# FOC_4.net
KiCad netlist of a schematic drawn in Altium Designer
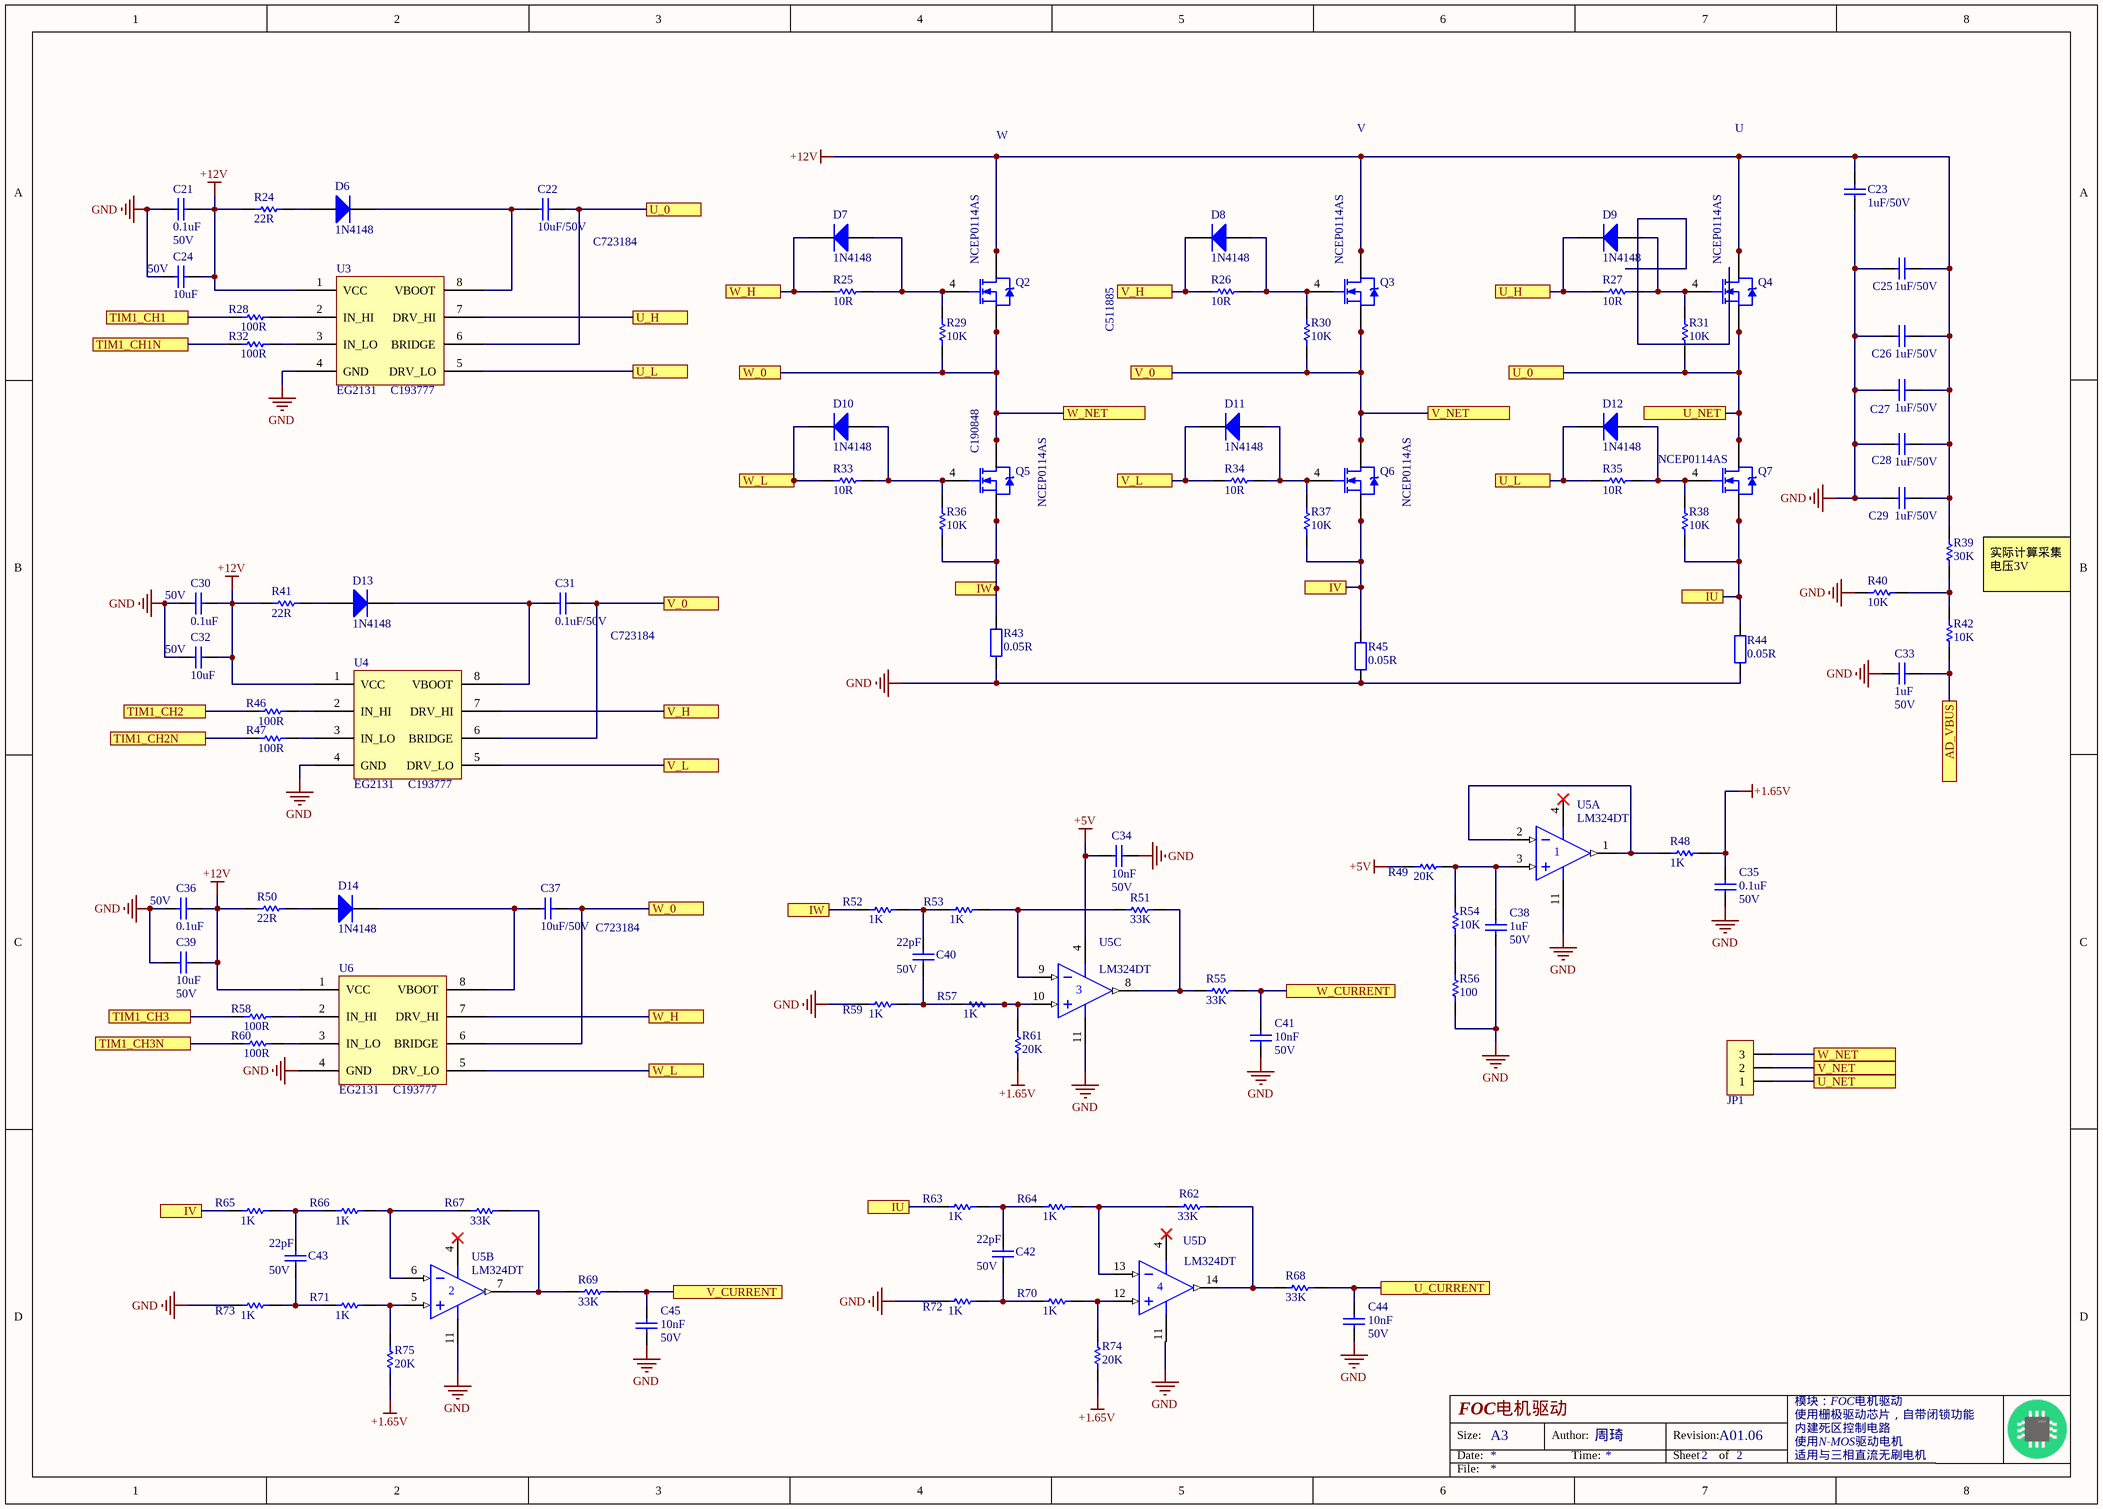
[diagram p0: FOC_4.SchDoc]

(export (version "E")
  (design (tool "Eeschema 10.0.6"))
  (components
    (comp (ref "C21")
      (value "0.1uF")
      (footprint "C0603_L")
      (fields (field (name "PARM") "50V"))
      (libsource (lib "Miscellaneous Devices") (part "Cap"))
    )
    (comp (ref "C22")
      (value "10uF/50V")
      (footprint "C0603_L")
      (description "C89632")
      (libsource (lib "Miscellaneous Devices") (part "Cap"))
    )
    (comp (ref "C23")
      (value "1uF/50V")
      (footprint "C1210_L")
      (libsource (lib "Miscellaneous Devices") (part "Cap"))
    )
    (comp (ref "C24")
      (value "10uF")
      (footprint "C0805_L")
      (fields (field (name "PARM") "50V"))
      (libsource (lib "Miscellaneous Devices") (part "Cap"))
    )
    (comp (ref "C25")
      (value "1uF/50V")
      (footprint "C1210_L")
      (libsource (lib "Miscellaneous Devices") (part "Cap"))
    )
    (comp (ref "C26")
      (value "1uF/50V")
      (footprint "C1210_L")
      (libsource (lib "Miscellaneous Devices") (part "Cap"))
    )
    (comp (ref "C27")
      (value "1uF/50V")
      (footprint "C1210_L")
      (libsource (lib "Miscellaneous Devices") (part "Cap"))
    )
    (comp (ref "C28")
      (value "1uF/50V")
      (footprint "C1210_L")
      (libsource (lib "Miscellaneous Devices") (part "Cap"))
    )
    (comp (ref "C29")
      (value "1uF/50V")
      (footprint "C1210_L")
      (libsource (lib "Miscellaneous Devices") (part "Cap"))
    )
    (comp (ref "C30")
      (value "0.1uF")
      (footprint "C0603_L")
      (fields (field (name "PARM") "50V"))
      (libsource (lib "Miscellaneous Devices") (part "Cap"))
    )
    (comp (ref "C31")
      (value "0.1uF/50V")
      (footprint "C0603_L")
      (description "C89632")
      (libsource (lib "Miscellaneous Devices") (part "Cap"))
    )
    (comp (ref "C32")
      (value "10uF")
      (footprint "C0805_L")
      (fields (field (name "PARM") "50V"))
      (libsource (lib "Miscellaneous Devices") (part "Cap"))
    )
    (comp (ref "C33")
      (value "1uF")
      (footprint "C0603_L")
      (fields (field (name "PARM") "50V"))
      (libsource (lib "Miscellaneous Devices") (part "Cap"))
    )
    (comp (ref "C34")
      (value "10nF")
      (footprint "C0603_L")
      (fields (field (name "PARM") "50V"))
      (libsource (lib "Miscellaneous Devices") (part "Cap"))
    )
    (comp (ref "C35")
      (value "0.1uF")
      (footprint "C0603_L")
      (fields (field (name "PARM") "50V"))
      (libsource (lib "Miscellaneous Devices") (part "Cap"))
    )
    (comp (ref "C36")
      (value "0.1uF")
      (footprint "C0603_L")
      (fields (field (name "PARM") "50V"))
      (libsource (lib "Miscellaneous Devices") (part "Cap"))
    )
    (comp (ref "C37")
      (value "10uF/50V")
      (footprint "C0603_L")
      (description "C89632")
      (libsource (lib "Miscellaneous Devices") (part "Cap"))
    )
    (comp (ref "C38")
      (value "1uF")
      (footprint "C0603_L")
      (fields (field (name "PARM") "50V"))
      (libsource (lib "Miscellaneous Devices") (part "Cap"))
    )
    (comp (ref "C39")
      (value "10uF")
      (footprint "C0805_L")
      (fields (field (name "PARM") "50V"))
      (libsource (lib "Miscellaneous Devices") (part "Cap"))
    )
    (comp (ref "C40")
      (value "22pF")
      (footprint "C0603_L")
      (fields (field (name "PARM") "50V"))
      (libsource (lib "Miscellaneous Devices") (part "Cap"))
    )
    (comp (ref "C41")
      (value "10nF")
      (footprint "C0603_L")
      (fields (field (name "PARM") "50V"))
      (libsource (lib "Miscellaneous Devices") (part "Cap"))
    )
    (comp (ref "C42")
      (value "22pF")
      (footprint "C0603_L")
      (fields (field (name "PARM") "50V"))
      (libsource (lib "Miscellaneous Devices") (part "Cap"))
    )
    (comp (ref "C43")
      (value "22pF")
      (footprint "C0603_L")
      (fields (field (name "PARM") "50V"))
      (libsource (lib "Miscellaneous Devices") (part "Cap"))
    )
    (comp (ref "C44")
      (value "10nF")
      (footprint "C0603_L")
      (fields (field (name "PARM") "50V"))
      (libsource (lib "Miscellaneous Devices") (part "Cap"))
    )
    (comp (ref "C45")
      (value "10nF")
      (footprint "C0603_L")
      (fields (field (name "PARM") "50V"))
      (libsource (lib "Miscellaneous Devices") (part "Cap"))
    )
    (comp (ref "D6")
      (value "1N4148")
      (footprint "SOD-123")
      (description "二极管")
      (libsource (lib "Miscellaneous Devices LC") (part "SOD-323 1N4148WS T4"))
    )
    (comp (ref "D7")
      (value "1N4148")
      (footprint "SOD-123")
      (description "二极管")
      (libsource (lib "Miscellaneous Devices LC") (part "SOD-323 1N4148WS T4"))
    )
    (comp (ref "D8")
      (value "1N4148")
      (footprint "SOD-123")
      (description "二极管")
      (libsource (lib "Miscellaneous Devices LC") (part "SOD-323 1N4148WS T4"))
    )
    (comp (ref "D9")
      (value "1N4148")
      (footprint "SOD-123")
      (description "二极管")
      (libsource (lib "Miscellaneous Devices LC") (part "SOD-323 1N4148WS T4"))
    )
    (comp (ref "D10")
      (value "1N4148")
      (footprint "SOD-123")
      (description "二极管")
      (libsource (lib "Miscellaneous Devices LC") (part "SOD-323 1N4148WS T4"))
    )
    (comp (ref "D11")
      (value "1N4148")
      (footprint "SOD-123")
      (description "二极管")
      (libsource (lib "Miscellaneous Devices LC") (part "SOD-323 1N4148WS T4"))
    )
    (comp (ref "D12")
      (value "1N4148")
      (footprint "SOD-123")
      (description "二极管")
      (libsource (lib "Miscellaneous Devices LC") (part "SOD-323 1N4148WS T4"))
    )
    (comp (ref "D13")
      (value "1N4148")
      (footprint "SOD-123")
      (description "二极管")
      (libsource (lib "Miscellaneous Devices LC") (part "SOD-323 1N4148WS T4"))
    )
    (comp (ref "D14")
      (value "1N4148")
      (footprint "SOD-123")
      (description "二极管")
      (libsource (lib "Miscellaneous Devices LC") (part "SOD-323 1N4148WS T4"))
    )
    (comp (ref "JP1")
      (value "HDR-1X3")
      (footprint "KF350-3P")
      (description "3P接插件")
      (fields (field (name "版权归属") "源创客"))
      (libsource (lib "接插件") (part "Header 3"))
    )
    (comp (ref "Q2")
      (value "NCEP0114AS")
      (footprint "SOP8")
      (description "C190848")
      (fields (field (name "PUBLISHER") "60V"))
      (libsource (lib "Miscellaneous Devices") (part "NMOS-2"))
    )
    (comp (ref "Q3")
      (value "NCEP0114AS")
      (footprint "SOP8")
      (description "C190848")
      (fields (field (name "PUBLISHER") "60V"))
      (libsource (lib "Miscellaneous Devices") (part "NMOS-2"))
    )
    (comp (ref "Q4")
      (value "NCEP0114AS")
      (footprint "SOP8")
      (description "C190848")
      (fields (field (name "PUBLISHER") "60V"))
      (libsource (lib "Miscellaneous Devices") (part "NMOS-2"))
    )
    (comp (ref "Q5")
      (value "NCEP0114AS")
      (footprint "SOP8")
      (description "C190848")
      (fields (field (name "PUBLISHER") "60V"))
      (libsource (lib "Miscellaneous Devices") (part "NMOS-2"))
    )
    (comp (ref "Q6")
      (value "NCEP0114AS")
      (footprint "SOP8")
      (description "C190848")
      (fields (field (name "PUBLISHER") "60V"))
      (libsource (lib "Miscellaneous Devices") (part "NMOS-2"))
    )
    (comp (ref "Q7")
      (value "NCEP0114AS")
      (footprint "SOP8")
      (description "C190848")
      (fields (field (name "PUBLISHER") "60V"))
      (libsource (lib "Miscellaneous Devices") (part "NMOS-2"))
    )
    (comp (ref "R24")
      (value "22R")
      (footprint "R0603_L")
      (description "Resistor")
      (libsource (lib "Miscellaneous Devices") (part "Res1"))
    )
    (comp (ref "R25")
      (value "10R")
      (footprint "R0603_L")
      (description "Resistor")
      (libsource (lib "Miscellaneous Devices") (part "Res1"))
    )
    (comp (ref "R26")
      (value "10R")
      (footprint "R0603_L")
      (description "Resistor")
      (libsource (lib "Miscellaneous Devices") (part "Res1"))
    )
    (comp (ref "R27")
      (value "10R")
      (footprint "R0603_L")
      (description "Resistor")
      (libsource (lib "Miscellaneous Devices") (part "Res1"))
    )
    (comp (ref "R28")
      (value "100R")
      (footprint "R0603_L")
      (description "Resistor")
      (libsource (lib "Miscellaneous Devices") (part "Res1"))
    )
    (comp (ref "R29")
      (value "10K")
      (footprint "R0603_L")
      (description "Resistor")
      (libsource (lib "Miscellaneous Devices") (part "Res1"))
    )
    (comp (ref "R30")
      (value "10K")
      (footprint "R0603_L")
      (description "Resistor")
      (libsource (lib "Miscellaneous Devices") (part "Res1"))
    )
    (comp (ref "R31")
      (value "10K")
      (footprint "R0603_L")
      (description "Resistor")
      (libsource (lib "Miscellaneous Devices") (part "Res1"))
    )
    (comp (ref "R32")
      (value "100R")
      (footprint "R0603_L")
      (description "Resistor")
      (libsource (lib "Miscellaneous Devices") (part "Res1"))
    )
    (comp (ref "R33")
      (value "10R")
      (footprint "R0603_L")
      (description "Resistor")
      (libsource (lib "Miscellaneous Devices") (part "Res1"))
    )
    (comp (ref "R34")
      (value "10R")
      (footprint "R0603_L")
      (description "Resistor")
      (libsource (lib "Miscellaneous Devices") (part "Res1"))
    )
    (comp (ref "R35")
      (value "10R")
      (footprint "R0603_L")
      (description "Resistor")
      (libsource (lib "Miscellaneous Devices") (part "Res1"))
    )
    (comp (ref "R36")
      (value "10K")
      (footprint "R0603_L")
      (description "Resistor")
      (libsource (lib "Miscellaneous Devices") (part "Res1"))
    )
    (comp (ref "R37")
      (value "10K")
      (footprint "R0603_L")
      (description "Resistor")
      (libsource (lib "Miscellaneous Devices") (part "Res1"))
    )
    (comp (ref "R38")
      (value "10K")
      (footprint "R0603_L")
      (description "Resistor")
      (libsource (lib "Miscellaneous Devices") (part "Res1"))
    )
    (comp (ref "R39")
      (value "30K")
      (footprint "R0603_L")
      (description "Resistor")
      (libsource (lib "Miscellaneous Devices") (part "Res1"))
    )
    (comp (ref "R40")
      (value "10K")
      (footprint "R0603_L")
      (description "Resistor")
      (libsource (lib "Miscellaneous Devices") (part "Res1"))
    )
    (comp (ref "R41")
      (value "22R")
      (footprint "R0603_L")
      (description "Resistor")
      (libsource (lib "Miscellaneous Devices") (part "Res1"))
    )
    (comp (ref "R42")
      (value "10K")
      (footprint "R0603_L")
      (description "Resistor")
      (libsource (lib "Miscellaneous Devices") (part "Res1"))
    )
    (comp (ref "R43")
      (value "0.05R")
      (footprint "R2512_L")
      (description "电流检测电阻")
      (fields (field (name "版权归属") "源创客"))
      (libsource (lib "电阻-电容-电感") (part "R-I"))
    )
    (comp (ref "R44")
      (value "0.05R")
      (footprint "R2512_L")
      (description "电流检测电阻")
      (fields (field (name "版权归属") "源创客"))
      (libsource (lib "电阻-电容-电感") (part "R-I"))
    )
    (comp (ref "R45")
      (value "0.05R")
      (footprint "R2512_L")
      (description "电流检测电阻")
      (fields (field (name "版权归属") "源创客"))
      (libsource (lib "电阻-电容-电感") (part "R-I"))
    )
    (comp (ref "R46")
      (value "100R")
      (footprint "R0603_L")
      (description "Resistor")
      (libsource (lib "Miscellaneous Devices") (part "Res1"))
    )
    (comp (ref "R47")
      (value "100R")
      (footprint "R0603_L")
      (description "Resistor")
      (libsource (lib "Miscellaneous Devices") (part "Res1"))
    )
    (comp (ref "R48")
      (value "1K")
      (footprint "R0603_L")
      (description "Resistor")
      (libsource (lib "Miscellaneous Devices") (part "Res1"))
    )
    (comp (ref "R49")
      (value "20K")
      (footprint "R0603_L")
      (description "Resistor")
      (libsource (lib "Miscellaneous Devices") (part "Res1"))
    )
    (comp (ref "R50")
      (value "22R")
      (footprint "R0603_L")
      (description "Resistor")
      (libsource (lib "Miscellaneous Devices") (part "Res1"))
    )
    (comp (ref "R51")
      (value "33K")
      (footprint "R0603_L")
      (description "Resistor")
      (libsource (lib "Miscellaneous Devices") (part "Res1"))
    )
    (comp (ref "R52")
      (value "1K")
      (footprint "R0603_L")
      (description "Resistor")
      (libsource (lib "Miscellaneous Devices") (part "Res1"))
    )
    (comp (ref "R53")
      (value "1K")
      (footprint "R0603_L")
      (description "Resistor")
      (libsource (lib "Miscellaneous Devices") (part "Res1"))
    )
    (comp (ref "R54")
      (value "10K")
      (footprint "R0603_L")
      (description "Resistor")
      (libsource (lib "Miscellaneous Devices") (part "Res1"))
    )
    (comp (ref "R55")
      (value "33K")
      (footprint "R0603_L")
      (description "Resistor")
      (libsource (lib "Miscellaneous Devices") (part "Res1"))
    )
    (comp (ref "R56")
      (value "100")
      (footprint "R0603_L")
      (description "Resistor")
      (libsource (lib "Miscellaneous Devices") (part "Res1"))
    )
    (comp (ref "R57")
      (value "1K")
      (footprint "R0603_L")
      (description "Resistor")
      (libsource (lib "Miscellaneous Devices") (part "Res1"))
    )
    (comp (ref "R58")
      (value "100R")
      (footprint "R0603_L")
      (description "Resistor")
      (libsource (lib "Miscellaneous Devices") (part "Res1"))
    )
    (comp (ref "R59")
      (value "1K")
      (footprint "R0603_L")
      (description "Resistor")
      (libsource (lib "Miscellaneous Devices") (part "Res1"))
    )
    (comp (ref "R60")
      (value "100R")
      (footprint "R0603_L")
      (description "Resistor")
      (libsource (lib "Miscellaneous Devices") (part "Res1"))
    )
    (comp (ref "R61")
      (value "20K")
      (footprint "R0603_L")
      (description "Resistor")
      (libsource (lib "Miscellaneous Devices") (part "Res1"))
    )
    (comp (ref "R62")
      (value "33K")
      (footprint "R0603_L")
      (description "Resistor")
      (libsource (lib "Miscellaneous Devices") (part "Res1"))
    )
    (comp (ref "R63")
      (value "1K")
      (footprint "R0603_L")
      (description "Resistor")
      (libsource (lib "Miscellaneous Devices") (part "Res1"))
    )
    (comp (ref "R64")
      (value "1K")
      (footprint "R0603_L")
      (description "Resistor")
      (libsource (lib "Miscellaneous Devices") (part "Res1"))
    )
    (comp (ref "R65")
      (value "1K")
      (footprint "R0603_L")
      (description "Resistor")
      (libsource (lib "Miscellaneous Devices") (part "Res1"))
    )
    (comp (ref "R66")
      (value "1K")
      (footprint "R0603_L")
      (description "Resistor")
      (libsource (lib "Miscellaneous Devices") (part "Res1"))
    )
    (comp (ref "R67")
      (value "33K")
      (footprint "R0603_L")
      (description "Resistor")
      (libsource (lib "Miscellaneous Devices") (part "Res1"))
    )
    (comp (ref "R68")
      (value "33K")
      (footprint "R0603_L")
      (description "Resistor")
      (libsource (lib "Miscellaneous Devices") (part "Res1"))
    )
    (comp (ref "R69")
      (value "33K")
      (footprint "R0603_L")
      (description "Resistor")
      (libsource (lib "Miscellaneous Devices") (part "Res1"))
    )
    (comp (ref "R70")
      (value "1K")
      (footprint "R0603_L")
      (description "Resistor")
      (libsource (lib "Miscellaneous Devices") (part "Res1"))
    )
    (comp (ref "R71")
      (value "1K")
      (footprint "R0603_L")
      (description "Resistor")
      (libsource (lib "Miscellaneous Devices") (part "Res1"))
    )
    (comp (ref "R72")
      (value "1K")
      (footprint "R0603_L")
      (description "Resistor")
      (libsource (lib "Miscellaneous Devices") (part "Res1"))
    )
    (comp (ref "R73")
      (value "1K")
      (footprint "R0603_L")
      (description "Resistor")
      (libsource (lib "Miscellaneous Devices") (part "Res1"))
    )
    (comp (ref "R74")
      (value "20K")
      (footprint "R0603_L")
      (description "Resistor")
      (libsource (lib "Miscellaneous Devices") (part "Res1"))
    )
    (comp (ref "R75")
      (value "20K")
      (footprint "R0603_L")
      (description "Resistor")
      (libsource (lib "Miscellaneous Devices") (part "Res1"))
    )
    (comp (ref "U3")
      (value "EG2131")
      (footprint "SOP8")
      (description "C193777")
      (fields (field (name "编号") "C193777"))
      (libsource (lib "Tang") (part "NCP5106BDR2G"))
    )
    (comp (ref "U4")
      (value "EG2131")
      (footprint "SOP8")
      (description "C193777")
      (fields (field (name "编号") "C193777"))
      (libsource (lib "Tang") (part "NCP5106BDR2G"))
    )
    (comp (ref "U5")
      (value "LM324DT")
      (footprint "SOIC-14")
      (description "运放")
      (libsource (lib "Miscellaneous Devices LC") (part "LM324DT_[C71035]"))
    )
    (comp (ref "U6")
      (value "EG2131")
      (footprint "SOP8")
      (description "C193777")
      (fields (field (name "编号") "C193777"))
      (libsource (lib "Tang") (part "NCP5106BDR2G"))
    )
  )
  (nets
    (net (code "1") (name "+1.65V") (class "Default")
      (node (ref "C35") (pin "2") (pinfunction "2_2") (pintype "passive"))
      (node (ref "R48") (pin "1") (pinfunction "1_1") (pintype "passive"))
      (node (ref "R61") (pin "1") (pinfunction "1_1") (pintype "passive"))
      (node (ref "R74") (pin "1") (pinfunction "1_1") (pintype "passive"))
      (node (ref "R75") (pin "1") (pinfunction "1_1") (pintype "passive"))
    )
    (net (code "2") (name "+5V") (class "Default")
      (node (ref "C34") (pin "2") (pinfunction "2_2") (pintype "passive"))
      (node (ref "R49") (pin "1") (pinfunction "1_1") (pintype "passive"))
      (node (ref "U5") (pin "4") (pinfunction "V+_4") (pintype "power_in"))
    )
    (net (code "3") (name "+12V") (class "Default")
      (node (ref "C21") (pin "1") (pinfunction "1_1") (pintype "passive"))
      (node (ref "C23") (pin "1") (pinfunction "1_1") (pintype "passive"))
      (node (ref "C24") (pin "1") (pinfunction "1_1") (pintype "passive"))
      (node (ref "C25") (pin "1") (pinfunction "1_1") (pintype "passive"))
      (node (ref "C26") (pin "1") (pinfunction "1_1") (pintype "passive"))
      (node (ref "C27") (pin "1") (pinfunction "1_1") (pintype "passive"))
      (node (ref "C28") (pin "1") (pinfunction "1_1") (pintype "passive"))
      (node (ref "C29") (pin "1") (pinfunction "1_1") (pintype "passive"))
      (node (ref "C30") (pin "1") (pinfunction "1_1") (pintype "passive"))
      (node (ref "C32") (pin "1") (pinfunction "1_1") (pintype "passive"))
      (node (ref "C36") (pin "1") (pinfunction "1_1") (pintype "passive"))
      (node (ref "C39") (pin "1") (pinfunction "1_1") (pintype "passive"))
      (node (ref "Q2") (pin "5") (pinfunction "D_5") (pintype "passive"))
      (node (ref "Q2") (pin "6") (pinfunction "D_6") (pintype "passive"))
      (node (ref "Q2") (pin "7") (pinfunction "D_7") (pintype "passive"))
      (node (ref "Q2") (pin "8") (pinfunction "D_8") (pintype "passive"))
      (node (ref "Q3") (pin "5") (pinfunction "D_5") (pintype "passive"))
      (node (ref "Q3") (pin "6") (pinfunction "D_6") (pintype "passive"))
      (node (ref "Q3") (pin "7") (pinfunction "D_7") (pintype "passive"))
      (node (ref "Q3") (pin "8") (pinfunction "D_8") (pintype "passive"))
      (node (ref "Q4") (pin "5") (pinfunction "D_5") (pintype "passive"))
      (node (ref "Q4") (pin "6") (pinfunction "D_6") (pintype "passive"))
      (node (ref "Q4") (pin "7") (pinfunction "D_7") (pintype "passive"))
      (node (ref "Q4") (pin "8") (pinfunction "D_8") (pintype "passive"))
      (node (ref "R24") (pin "1") (pinfunction "1_1") (pintype "passive"))
      (node (ref "R39") (pin "2") (pinfunction "2_2") (pintype "passive"))
      (node (ref "R41") (pin "1") (pinfunction "1_1") (pintype "passive"))
      (node (ref "R50") (pin "1") (pinfunction "1_1") (pintype "passive"))
      (node (ref "U3") (pin "1") (pinfunction "VCC_1") (pintype "passive"))
      (node (ref "U4") (pin "1") (pinfunction "VCC_1") (pintype "passive"))
      (node (ref "U6") (pin "1") (pinfunction "VCC_1") (pintype "passive"))
    )
    (net (code "4") (name "/AD_VBUS") (class "Default")
      (node (ref "C33") (pin "2") (pinfunction "2_2") (pintype "passive"))
      (node (ref "R42") (pin "2") (pinfunction "2_2") (pintype "passive"))
    )
    (net (code "5") (name "/IU") (class "Default")
      (node (ref "Q7") (pin "1") (pinfunction "S_1") (pintype "passive"))
      (node (ref "Q7") (pin "2") (pinfunction "S_2") (pintype "passive"))
      (node (ref "Q7") (pin "3") (pinfunction "S_3") (pintype "passive"))
      (node (ref "R38") (pin "1") (pinfunction "1_1") (pintype "passive"))
      (node (ref "R44") (pin "2") (pinfunction "2_2") (pintype "passive"))
      (node (ref "R63") (pin "1") (pinfunction "1_1") (pintype "passive"))
    )
    (net (code "6") (name "/IV") (class "Default")
      (node (ref "Q6") (pin "1") (pinfunction "S_1") (pintype "passive"))
      (node (ref "Q6") (pin "2") (pinfunction "S_2") (pintype "passive"))
      (node (ref "Q6") (pin "3") (pinfunction "S_3") (pintype "passive"))
      (node (ref "R37") (pin "1") (pinfunction "1_1") (pintype "passive"))
      (node (ref "R45") (pin "2") (pinfunction "2_2") (pintype "passive"))
      (node (ref "R65") (pin "1") (pinfunction "1_1") (pintype "passive"))
    )
    (net (code "7") (name "/IW") (class "Default")
      (node (ref "Q5") (pin "1") (pinfunction "S_1") (pintype "passive"))
      (node (ref "Q5") (pin "2") (pinfunction "S_2") (pintype "passive"))
      (node (ref "Q5") (pin "3") (pinfunction "S_3") (pintype "passive"))
      (node (ref "R36") (pin "1") (pinfunction "1_1") (pintype "passive"))
      (node (ref "R43") (pin "2") (pinfunction "2_2") (pintype "passive"))
      (node (ref "R52") (pin "1") (pinfunction "1_1") (pintype "passive"))
    )
    (net (code "8") (name "/TIM1_CH1") (class "Default")
      (node (ref "R28") (pin "1") (pinfunction "1_1") (pintype "passive"))
    )
    (net (code "9") (name "/TIM1_CH1N") (class "Default")
      (node (ref "R32") (pin "1") (pinfunction "1_1") (pintype "passive"))
    )
    (net (code "10") (name "/TIM1_CH2") (class "Default")
      (node (ref "R46") (pin "1") (pinfunction "1_1") (pintype "passive"))
    )
    (net (code "11") (name "/TIM1_CH2N") (class "Default")
      (node (ref "R47") (pin "1") (pinfunction "1_1") (pintype "passive"))
    )
    (net (code "12") (name "/TIM1_CH3") (class "Default")
      (node (ref "R58") (pin "1") (pinfunction "1_1") (pintype "passive"))
    )
    (net (code "13") (name "/TIM1_CH3N") (class "Default")
      (node (ref "R60") (pin "1") (pinfunction "1_1") (pintype "passive"))
    )
    (net (code "14") (name "/U_0") (class "Default")
      (node (ref "C22") (pin "1") (pinfunction "1_1") (pintype "passive"))
      (node (ref "JP1") (pin "1") (pinfunction "1_1") (pintype "passive"))
      (node (ref "Q4") (pin "1") (pinfunction "S_1") (pintype "passive"))
      (node (ref "Q4") (pin "2") (pinfunction "S_2") (pintype "passive"))
      (node (ref "Q4") (pin "3") (pinfunction "S_3") (pintype "passive"))
      (node (ref "Q7") (pin "5") (pinfunction "D_5") (pintype "passive"))
      (node (ref "Q7") (pin "6") (pinfunction "D_6") (pintype "passive"))
      (node (ref "Q7") (pin "7") (pinfunction "D_7") (pintype "passive"))
      (node (ref "Q7") (pin "8") (pinfunction "D_8") (pintype "passive"))
      (node (ref "R31") (pin "1") (pinfunction "1_1") (pintype "passive"))
      (node (ref "U3") (pin "6") (pinfunction "BRIDGE_6") (pintype "passive"))
    )
    (net (code "15") (name "/U_CURRENT") (class "Default")
      (node (ref "C44") (pin "2") (pinfunction "2_2") (pintype "passive"))
      (node (ref "R68") (pin "1") (pinfunction "1_1") (pintype "passive"))
    )
    (net (code "16") (name "/U_H") (class "Default")
      (node (ref "D9") (pin "2") (pinfunction "K_2") (pintype "passive"))
      (node (ref "R27") (pin "1") (pinfunction "1_1") (pintype "passive"))
      (node (ref "U3") (pin "7") (pinfunction "DRV_HI_7") (pintype "passive"))
    )
    (net (code "17") (name "/U_L") (class "Default")
      (node (ref "D12") (pin "2") (pinfunction "K_2") (pintype "passive"))
      (node (ref "R35") (pin "1") (pinfunction "1_1") (pintype "passive"))
      (node (ref "U3") (pin "5") (pinfunction "DRV_LO_5") (pintype "passive"))
    )
    (net (code "18") (name "/V_0") (class "Default")
      (node (ref "C31") (pin "1") (pinfunction "1_1") (pintype "passive"))
      (node (ref "JP1") (pin "2") (pinfunction "2_2") (pintype "passive"))
      (node (ref "Q3") (pin "1") (pinfunction "S_1") (pintype "passive"))
      (node (ref "Q3") (pin "2") (pinfunction "S_2") (pintype "passive"))
      (node (ref "Q3") (pin "3") (pinfunction "S_3") (pintype "passive"))
      (node (ref "Q6") (pin "5") (pinfunction "D_5") (pintype "passive"))
      (node (ref "Q6") (pin "6") (pinfunction "D_6") (pintype "passive"))
      (node (ref "Q6") (pin "7") (pinfunction "D_7") (pintype "passive"))
      (node (ref "Q6") (pin "8") (pinfunction "D_8") (pintype "passive"))
      (node (ref "R30") (pin "1") (pinfunction "1_1") (pintype "passive"))
      (node (ref "U4") (pin "6") (pinfunction "BRIDGE_6") (pintype "passive"))
    )
    (net (code "19") (name "/V_CURRENT") (class "Default")
      (node (ref "C45") (pin "2") (pinfunction "2_2") (pintype "passive"))
      (node (ref "R69") (pin "1") (pinfunction "1_1") (pintype "passive"))
    )
    (net (code "20") (name "/V_H") (class "Default")
      (node (ref "D8") (pin "2") (pinfunction "K_2") (pintype "passive"))
      (node (ref "R26") (pin "1") (pinfunction "1_1") (pintype "passive"))
      (node (ref "U4") (pin "7") (pinfunction "DRV_HI_7") (pintype "passive"))
    )
    (net (code "21") (name "/V_L") (class "Default")
      (node (ref "D11") (pin "2") (pinfunction "K_2") (pintype "passive"))
      (node (ref "R34") (pin "1") (pinfunction "1_1") (pintype "passive"))
      (node (ref "U4") (pin "5") (pinfunction "DRV_LO_5") (pintype "passive"))
    )
    (net (code "22") (name "/W_0") (class "Default")
      (node (ref "C37") (pin "1") (pinfunction "1_1") (pintype "passive"))
      (node (ref "JP1") (pin "3") (pinfunction "3_3") (pintype "passive"))
      (node (ref "Q2") (pin "1") (pinfunction "S_1") (pintype "passive"))
      (node (ref "Q2") (pin "2") (pinfunction "S_2") (pintype "passive"))
      (node (ref "Q2") (pin "3") (pinfunction "S_3") (pintype "passive"))
      (node (ref "Q5") (pin "5") (pinfunction "D_5") (pintype "passive"))
      (node (ref "Q5") (pin "6") (pinfunction "D_6") (pintype "passive"))
      (node (ref "Q5") (pin "7") (pinfunction "D_7") (pintype "passive"))
      (node (ref "Q5") (pin "8") (pinfunction "D_8") (pintype "passive"))
      (node (ref "R29") (pin "1") (pinfunction "1_1") (pintype "passive"))
      (node (ref "U6") (pin "6") (pinfunction "BRIDGE_6") (pintype "passive"))
    )
    (net (code "23") (name "/W_CURRENT") (class "Default")
      (node (ref "C41") (pin "2") (pinfunction "2_2") (pintype "passive"))
      (node (ref "R55") (pin "1") (pinfunction "1_1") (pintype "passive"))
    )
    (net (code "24") (name "/W_H") (class "Default")
      (node (ref "D7") (pin "2") (pinfunction "K_2") (pintype "passive"))
      (node (ref "R25") (pin "1") (pinfunction "1_1") (pintype "passive"))
      (node (ref "U6") (pin "7") (pinfunction "DRV_HI_7") (pintype "passive"))
    )
    (net (code "25") (name "/W_L") (class "Default")
      (node (ref "D10") (pin "2") (pinfunction "K_2") (pintype "passive"))
      (node (ref "R33") (pin "1") (pinfunction "1_1") (pintype "passive"))
      (node (ref "U6") (pin "5") (pinfunction "DRV_LO_5") (pintype "passive"))
    )
    (net (code "26") (name "GND") (class "Default")
      (node (ref "C21") (pin "2") (pinfunction "2_2") (pintype "passive"))
      (node (ref "C23") (pin "2") (pinfunction "2_2") (pintype "passive"))
      (node (ref "C24") (pin "2") (pinfunction "2_2") (pintype "passive"))
      (node (ref "C25") (pin "2") (pinfunction "2_2") (pintype "passive"))
      (node (ref "C26") (pin "2") (pinfunction "2_2") (pintype "passive"))
      (node (ref "C27") (pin "2") (pinfunction "2_2") (pintype "passive"))
      (node (ref "C28") (pin "2") (pinfunction "2_2") (pintype "passive"))
      (node (ref "C29") (pin "2") (pinfunction "2_2") (pintype "passive"))
      (node (ref "C30") (pin "2") (pinfunction "2_2") (pintype "passive"))
      (node (ref "C32") (pin "2") (pinfunction "2_2") (pintype "passive"))
      (node (ref "C33") (pin "1") (pinfunction "1_1") (pintype "passive"))
      (node (ref "C34") (pin "1") (pinfunction "1_1") (pintype "passive"))
      (node (ref "C35") (pin "1") (pinfunction "1_1") (pintype "passive"))
      (node (ref "C36") (pin "2") (pinfunction "2_2") (pintype "passive"))
      (node (ref "C38") (pin "1") (pinfunction "1_1") (pintype "passive"))
      (node (ref "C39") (pin "2") (pinfunction "2_2") (pintype "passive"))
      (node (ref "C41") (pin "1") (pinfunction "1_1") (pintype "passive"))
      (node (ref "C44") (pin "1") (pinfunction "1_1") (pintype "passive"))
      (node (ref "C45") (pin "1") (pinfunction "1_1") (pintype "passive"))
      (node (ref "R40") (pin "2") (pinfunction "2_2") (pintype "passive"))
      (node (ref "R43") (pin "1") (pinfunction "1_1") (pintype "passive"))
      (node (ref "R44") (pin "1") (pinfunction "1_1") (pintype "passive"))
      (node (ref "R45") (pin "1") (pinfunction "1_1") (pintype "passive"))
      (node (ref "R56") (pin "1") (pinfunction "1_1") (pintype "passive"))
      (node (ref "R59") (pin "1") (pinfunction "1_1") (pintype "passive"))
      (node (ref "R72") (pin "1") (pinfunction "1_1") (pintype "passive"))
      (node (ref "R73") (pin "1") (pinfunction "1_1") (pintype "passive"))
      (node (ref "U3") (pin "4") (pinfunction "GND_4") (pintype "passive"))
      (node (ref "U4") (pin "4") (pinfunction "GND_4") (pintype "passive"))
      (node (ref "U5") (pin "11") (pinfunction "V-_11") (pintype "power_in"))
      (node (ref "U6") (pin "4") (pinfunction "GND_4") (pintype "passive"))
    )
    (net (code "27") (name "Net-(C40-Pad1)") (class "Default")
      (node (ref "C40") (pin "1") (pinfunction "1_1") (pintype "passive"))
      (node (ref "R52") (pin "2") (pinfunction "2_2") (pintype "passive"))
      (node (ref "R53") (pin "1") (pinfunction "1_1") (pintype "passive"))
    )
    (net (code "28") (name "Net-(C40-Pad2)") (class "Default")
      (node (ref "C40") (pin "2") (pinfunction "2_2") (pintype "passive"))
      (node (ref "R57") (pin "1") (pinfunction "1_1") (pintype "passive"))
      (node (ref "R59") (pin "2") (pinfunction "2_2") (pintype "passive"))
    )
    (net (code "29") (name "Net-(C42-Pad1)") (class "Default")
      (node (ref "C42") (pin "1") (pinfunction "1_1") (pintype "passive"))
      (node (ref "R63") (pin "2") (pinfunction "2_2") (pintype "passive"))
      (node (ref "R64") (pin "1") (pinfunction "1_1") (pintype "passive"))
    )
    (net (code "30") (name "Net-(C42-Pad2)") (class "Default")
      (node (ref "C42") (pin "2") (pinfunction "2_2") (pintype "passive"))
      (node (ref "R70") (pin "1") (pinfunction "1_1") (pintype "passive"))
      (node (ref "R72") (pin "2") (pinfunction "2_2") (pintype "passive"))
    )
    (net (code "31") (name "Net-(C43-Pad1)") (class "Default")
      (node (ref "C43") (pin "1") (pinfunction "1_1") (pintype "passive"))
      (node (ref "R65") (pin "2") (pinfunction "2_2") (pintype "passive"))
      (node (ref "R66") (pin "1") (pinfunction "1_1") (pintype "passive"))
    )
    (net (code "32") (name "Net-(C43-Pad2)") (class "Default")
      (node (ref "C43") (pin "2") (pinfunction "2_2") (pintype "passive"))
      (node (ref "R71") (pin "1") (pinfunction "1_1") (pintype "passive"))
      (node (ref "R73") (pin "2") (pinfunction "2_2") (pintype "passive"))
    )
    (net (code "33") (name "Net-(D6-A)") (class "Default")
      (node (ref "D6") (pin "1") (pinfunction "A_1") (pintype "passive"))
      (node (ref "R24") (pin "2") (pinfunction "2_2") (pintype "passive"))
    )
    (net (code "34") (name "Net-(D6-K)") (class "Default")
      (node (ref "C22") (pin "2") (pinfunction "2_2") (pintype "passive"))
      (node (ref "D6") (pin "2") (pinfunction "K_2") (pintype "passive"))
      (node (ref "U3") (pin "8") (pinfunction "VBOOT_8") (pintype "passive"))
    )
    (net (code "35") (name "Net-(D7-A)") (class "Default")
      (node (ref "D7") (pin "1") (pinfunction "A_1") (pintype "passive"))
      (node (ref "Q2") (pin "4") (pinfunction "G_4") (pintype "passive"))
      (node (ref "R25") (pin "2") (pinfunction "2_2") (pintype "passive"))
      (node (ref "R29") (pin "2") (pinfunction "2_2") (pintype "passive"))
    )
    (net (code "36") (name "Net-(D8-A)") (class "Default")
      (node (ref "D8") (pin "1") (pinfunction "A_1") (pintype "passive"))
      (node (ref "Q3") (pin "4") (pinfunction "G_4") (pintype "passive"))
      (node (ref "R26") (pin "2") (pinfunction "2_2") (pintype "passive"))
      (node (ref "R30") (pin "2") (pinfunction "2_2") (pintype "passive"))
    )
    (net (code "37") (name "Net-(D9-A)") (class "Default")
      (node (ref "D9") (pin "1") (pinfunction "A_1") (pintype "passive"))
      (node (ref "Q4") (pin "4") (pinfunction "G_4") (pintype "passive"))
      (node (ref "R27") (pin "2") (pinfunction "2_2") (pintype "passive"))
      (node (ref "R31") (pin "2") (pinfunction "2_2") (pintype "passive"))
    )
    (net (code "38") (name "Net-(D10-A)") (class "Default")
      (node (ref "D10") (pin "1") (pinfunction "A_1") (pintype "passive"))
      (node (ref "Q5") (pin "4") (pinfunction "G_4") (pintype "passive"))
      (node (ref "R33") (pin "2") (pinfunction "2_2") (pintype "passive"))
      (node (ref "R36") (pin "2") (pinfunction "2_2") (pintype "passive"))
    )
    (net (code "39") (name "Net-(D11-A)") (class "Default")
      (node (ref "D11") (pin "1") (pinfunction "A_1") (pintype "passive"))
      (node (ref "Q6") (pin "4") (pinfunction "G_4") (pintype "passive"))
      (node (ref "R34") (pin "2") (pinfunction "2_2") (pintype "passive"))
      (node (ref "R37") (pin "2") (pinfunction "2_2") (pintype "passive"))
    )
    (net (code "40") (name "Net-(D12-A)") (class "Default")
      (node (ref "D12") (pin "1") (pinfunction "A_1") (pintype "passive"))
      (node (ref "Q7") (pin "4") (pinfunction "G_4") (pintype "passive"))
      (node (ref "R35") (pin "2") (pinfunction "2_2") (pintype "passive"))
      (node (ref "R38") (pin "2") (pinfunction "2_2") (pintype "passive"))
    )
    (net (code "41") (name "Net-(D13-A)") (class "Default")
      (node (ref "D13") (pin "1") (pinfunction "A_1") (pintype "passive"))
      (node (ref "R41") (pin "2") (pinfunction "2_2") (pintype "passive"))
    )
    (net (code "42") (name "Net-(D13-K)") (class "Default")
      (node (ref "C31") (pin "2") (pinfunction "2_2") (pintype "passive"))
      (node (ref "D13") (pin "2") (pinfunction "K_2") (pintype "passive"))
      (node (ref "U4") (pin "8") (pinfunction "VBOOT_8") (pintype "passive"))
    )
    (net (code "43") (name "Net-(D14-A)") (class "Default")
      (node (ref "D14") (pin "1") (pinfunction "A_1") (pintype "passive"))
      (node (ref "R50") (pin "2") (pinfunction "2_2") (pintype "passive"))
    )
    (net (code "44") (name "Net-(D14-K)") (class "Default")
      (node (ref "C37") (pin "2") (pinfunction "2_2") (pintype "passive"))
      (node (ref "D14") (pin "2") (pinfunction "K_2") (pintype "passive"))
      (node (ref "U6") (pin "8") (pinfunction "VBOOT_8") (pintype "passive"))
    )
    (net (code "45") (name "Net-(R39-Pad1)") (class "Default")
      (node (ref "R39") (pin "1") (pinfunction "1_1") (pintype "passive"))
      (node (ref "R40") (pin "1") (pinfunction "1_1") (pintype "passive"))
      (node (ref "R42") (pin "1") (pinfunction "1_1") (pintype "passive"))
    )
    (net (code "46") (name "Net-(R54-Pad1)") (class "Default")
      (node (ref "R54") (pin "1") (pinfunction "1_1") (pintype "passive"))
      (node (ref "R56") (pin "2") (pinfunction "2_2") (pintype "passive"))
    )
    (net (code "47") (name "Net-(U3-IN_HI)") (class "Default")
      (node (ref "R28") (pin "2") (pinfunction "2_2") (pintype "passive"))
      (node (ref "U3") (pin "2") (pinfunction "IN_HI_2") (pintype "passive"))
    )
    (net (code "48") (name "Net-(U3-IN_LO)") (class "Default")
      (node (ref "R32") (pin "2") (pinfunction "2_2") (pintype "passive"))
      (node (ref "U3") (pin "3") (pinfunction "IN_LO_3") (pintype "passive"))
    )
    (net (code "49") (name "Net-(U4-IN_HI)") (class "Default")
      (node (ref "R46") (pin "2") (pinfunction "2_2") (pintype "passive"))
      (node (ref "U4") (pin "2") (pinfunction "IN_HI_2") (pintype "passive"))
    )
    (net (code "50") (name "Net-(U4-IN_LO)") (class "Default")
      (node (ref "R47") (pin "2") (pinfunction "2_2") (pintype "passive"))
      (node (ref "U4") (pin "3") (pinfunction "IN_LO_3") (pintype "passive"))
    )
    (net (code "51") (name "Net-(U5A-IN+)") (class "Default")
      (node (ref "C38") (pin "2") (pinfunction "2_2") (pintype "passive"))
      (node (ref "R49") (pin "2") (pinfunction "2_2") (pintype "passive"))
      (node (ref "R54") (pin "2") (pinfunction "2_2") (pintype "passive"))
      (node (ref "U5") (pin "3") (pinfunction "IN+_3") (pintype "input"))
    )
    (net (code "52") (name "Net-(U5A-IN-)") (class "Default")
      (node (ref "R48") (pin "2") (pinfunction "2_2") (pintype "passive"))
      (node (ref "U5") (pin "1") (pinfunction "OUT_1") (pintype "output"))
      (node (ref "U5") (pin "2") (pinfunction "IN-_2") (pintype "input"))
    )
    (net (code "53") (name "Net-(U5B-IN+)") (class "Default")
      (node (ref "R71") (pin "2") (pinfunction "2_2") (pintype "passive"))
      (node (ref "R75") (pin "2") (pinfunction "2_2") (pintype "passive"))
      (node (ref "U5") (pin "5") (pinfunction "IN+_5") (pintype "input"))
    )
    (net (code "54") (name "Net-(U5B-IN-)") (class "Default")
      (node (ref "R66") (pin "2") (pinfunction "2_2") (pintype "passive"))
      (node (ref "R67") (pin "1") (pinfunction "1_1") (pintype "passive"))
      (node (ref "U5") (pin "6") (pinfunction "IN-_6") (pintype "input"))
    )
    (net (code "55") (name "Net-(U5B-OUT)") (class "Default")
      (node (ref "R67") (pin "2") (pinfunction "2_2") (pintype "passive"))
      (node (ref "R69") (pin "2") (pinfunction "2_2") (pintype "passive"))
      (node (ref "U5") (pin "7") (pinfunction "OUT_7") (pintype "output"))
    )
    (net (code "56") (name "Net-(U5C-IN+)") (class "Default")
      (node (ref "R57") (pin "2") (pinfunction "2_2") (pintype "passive"))
      (node (ref "R61") (pin "2") (pinfunction "2_2") (pintype "passive"))
      (node (ref "U5") (pin "10") (pinfunction "IN+_10") (pintype "input"))
    )
    (net (code "57") (name "Net-(U5C-IN-)") (class "Default")
      (node (ref "R51") (pin "1") (pinfunction "1_1") (pintype "passive"))
      (node (ref "R53") (pin "2") (pinfunction "2_2") (pintype "passive"))
      (node (ref "U5") (pin "9") (pinfunction "IN-_9") (pintype "input"))
    )
    (net (code "58") (name "Net-(U5C-OUT)") (class "Default")
      (node (ref "R51") (pin "2") (pinfunction "2_2") (pintype "passive"))
      (node (ref "R55") (pin "2") (pinfunction "2_2") (pintype "passive"))
      (node (ref "U5") (pin "8") (pinfunction "OUT_8") (pintype "output"))
    )
    (net (code "59") (name "Net-(U5D-IN+)") (class "Default")
      (node (ref "R70") (pin "2") (pinfunction "2_2") (pintype "passive"))
      (node (ref "R74") (pin "2") (pinfunction "2_2") (pintype "passive"))
      (node (ref "U5") (pin "12") (pinfunction "IN+_12") (pintype "input"))
    )
    (net (code "60") (name "Net-(U5D-IN-)") (class "Default")
      (node (ref "R62") (pin "1") (pinfunction "1_1") (pintype "passive"))
      (node (ref "R64") (pin "2") (pinfunction "2_2") (pintype "passive"))
      (node (ref "U5") (pin "13") (pinfunction "IN-_13") (pintype "input"))
    )
    (net (code "61") (name "Net-(U5D-OUT)") (class "Default")
      (node (ref "R62") (pin "2") (pinfunction "2_2") (pintype "passive"))
      (node (ref "R68") (pin "2") (pinfunction "2_2") (pintype "passive"))
      (node (ref "U5") (pin "14") (pinfunction "OUT_14") (pintype "output"))
    )
    (net (code "62") (name "Net-(U6-IN_HI)") (class "Default")
      (node (ref "R58") (pin "2") (pinfunction "2_2") (pintype "passive"))
      (node (ref "U6") (pin "2") (pinfunction "IN_HI_2") (pintype "passive"))
    )
    (net (code "63") (name "Net-(U6-IN_LO)") (class "Default")
      (node (ref "R60") (pin "2") (pinfunction "2_2") (pintype "passive"))
      (node (ref "U6") (pin "3") (pinfunction "IN_LO_3") (pintype "passive"))
    )
    (net (code "64") (name "unconnected-(U5A-V+-Pad4)") (class "Default")
      (node (ref "U5") (pin "4") (pinfunction "V+_4") (pintype "power_in+no_connect"))
    )
    (net (code "65") (name "unconnected-(U5B-V+-Pad4)") (class "Default")
      (node (ref "U5") (pin "4") (pinfunction "V+_4") (pintype "power_in+no_connect"))
    )
    (net (code "66") (name "unconnected-(U5D-V+-Pad4)") (class "Default")
      (node (ref "U5") (pin "4") (pinfunction "V+_4") (pintype "power_in+no_connect"))
    )
    (net (code "67") (name "unconnected-(U5D-V--Pad11)") (class "Default")
      (node (ref "U5") (pin "11") (pinfunction "V-_11") (pintype "power_in"))
    )
  )
)
